# blumentopf_feuchte_messer.net
KiCad netlist of a schematic drawn in EAGLE
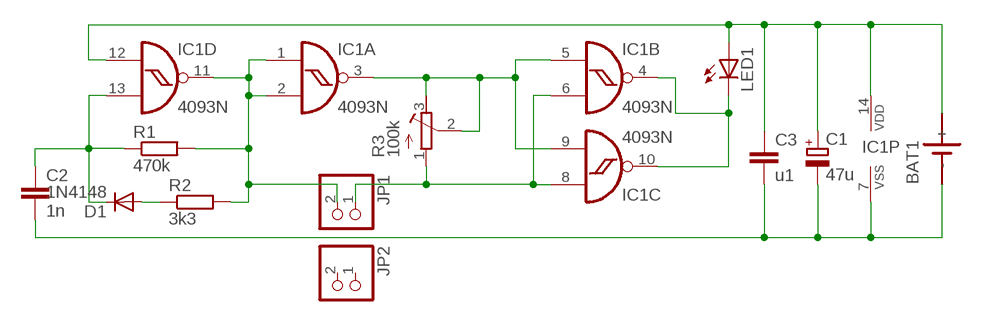
[diagram p0: schematic, sheet 1]

(export (version "E")
  (design (tool "Eeschema 10.0.6"))
  (components
    (comp (ref "BAT1")
      (value "SN2032")
      (footprint "eagle-import:SN2032")
      (libsource (lib "eagle-import") (part "SN2032"))
    )
    (comp (ref "C1")
      (value "47u")
      (footprint "eagle-import:E2,5-5")
      (libsource (lib "eagle-import") (part "CPOL-EUE2.5-5"))
    )
    (comp (ref "C2")
      (value "1n")
      (footprint "eagle-import:C025-025X050")
      (libsource (lib "eagle-import") (part "C-EU025-025X050"))
    )
    (comp (ref "C3")
      (value "u1")
      (footprint "eagle-import:C025-025X050")
      (libsource (lib "eagle-import") (part "C-EU025-025X050"))
    )
    (comp (ref "D1")
      (value "1N4148")
      (footprint "eagle-import:D-2.5")
      (libsource (lib "eagle-import") (part "DIODE-D-2.5"))
    )
    (comp (ref "IC1")
      (value "4093N")
      (footprint "eagle-import:DIL14")
      (libsource (lib "eagle-import") (part "4093N"))
    )
    (comp (ref "JP1")
      (value "PINHD-1X2")
      (footprint "eagle-import:1X02")
      (libsource (lib "eagle-import") (part "PINHD-1X2"))
    )
    (comp (ref "JP2")
      (value "PINHD-1X2")
      (footprint "eagle-import:1X02")
      (libsource (lib "eagle-import") (part "PINHD-1X2"))
    )
    (comp (ref "LED1")
      (value "LED3MM")
      (footprint "eagle-import:LED3MM")
      (libsource (lib "eagle-import") (part "LED3MM"))
    )
    (comp (ref "R1")
      (value "470k")
      (footprint "eagle-import:0207_2V")
      (libsource (lib "eagle-import") (part "R-EU_0207/2V"))
    )
    (comp (ref "R2")
      (value "3k3")
      (footprint "eagle-import:0207_2V")
      (libsource (lib "eagle-import") (part "R-EU_0207/2V"))
    )
    (comp (ref "R3")
      (value "100k")
      (footprint "eagle-import:RTRIM64X")
      (libsource (lib "eagle-import") (part "R-TRIMM64X"))
    )
  )
  (nets
    (net (code "1") (name "Net-(D1-PadA)") (class "Default")
      (node (ref "D1") (pin "A") (pinfunction "A_A") (pintype "passive"))
      (node (ref "R2") (pin "1") (pinfunction "1_1") (pintype "passive"))
    )
    (net (code "2") (name "Net-(IC1A-I0)") (class "Default")
      (node (ref "IC1") (pin "1") (pinfunction "I0_1") (pintype "input"))
      (node (ref "IC1") (pin "11") (pinfunction "O_11") (pintype "output"))
      (node (ref "IC1") (pin "2") (pinfunction "I1_2") (pintype "input"))
      (node (ref "JP1") (pin "2") (pinfunction "2_2") (pintype "passive"))
      (node (ref "R1") (pin "2") (pinfunction "2_2") (pintype "passive"))
      (node (ref "R2") (pin "2") (pinfunction "2_2") (pintype "passive"))
    )
    (net (code "3") (name "Net-(IC1A-O)") (class "Default")
      (node (ref "IC1") (pin "3") (pinfunction "O_3") (pintype "output"))
      (node (ref "IC1") (pin "5") (pinfunction "I0_5") (pintype "input"))
      (node (ref "IC1") (pin "9") (pinfunction "I1_9") (pintype "input"))
      (node (ref "R3") (pin "2") (pinfunction "S_2") (pintype "passive"))
      (node (ref "R3") (pin "3") (pinfunction "E_3") (pintype "passive"))
    )
    (net (code "4") (name "Net-(IC1B-I1)") (class "Default")
      (node (ref "IC1") (pin "6") (pinfunction "I1_6") (pintype "input"))
      (node (ref "IC1") (pin "8") (pinfunction "I0_8") (pintype "input"))
      (node (ref "JP1") (pin "1") (pinfunction "1_1") (pintype "passive"))
      (node (ref "R3") (pin "1") (pinfunction "A_1") (pintype "passive"))
    )
    (net (code "5") (name "Net-(IC1B-O)") (class "Default")
      (node (ref "IC1") (pin "10") (pinfunction "O_10") (pintype "output"))
      (node (ref "IC1") (pin "4") (pinfunction "O_4") (pintype "output"))
      (node (ref "LED1") (pin "K") (pinfunction "C_K") (pintype "passive"))
    )
    (net (code "6") (name "Net-(IC1D-I0)") (class "Default")
      (node (ref "BAT1") (pin "+") (pinfunction "+_+") (pintype "passive"))
      (node (ref "C1") (pin "+") (pinfunction "+_+") (pintype "passive"))
      (node (ref "C3") (pin "1") (pinfunction "1_1") (pintype "passive"))
      (node (ref "IC1") (pin "12") (pinfunction "I0_12") (pintype "input"))
      (node (ref "IC1") (pin "14") (pinfunction "VDD_14") (pintype "power_in"))
      (node (ref "LED1") (pin "A") (pinfunction "A_A") (pintype "passive"))
    )
    (net (code "7") (name "Net-(IC1D-I1)") (class "Default")
      (node (ref "C2") (pin "1") (pinfunction "1_1") (pintype "passive"))
      (node (ref "D1") (pin "C") (pinfunction "C_C") (pintype "passive"))
      (node (ref "IC1") (pin "13") (pinfunction "I1_13") (pintype "input"))
      (node (ref "R1") (pin "1") (pinfunction "1_1") (pintype "passive"))
    )
    (net (code "8") (name "Net-(IC1E-VSS)") (class "Default")
      (node (ref "BAT1") (pin "-") (pinfunction "-_-") (pintype "passive"))
      (node (ref "C1") (pin "-") (pinfunction "-_-") (pintype "passive"))
      (node (ref "C2") (pin "2") (pinfunction "2_2") (pintype "passive"))
      (node (ref "C3") (pin "2") (pinfunction "2_2") (pintype "passive"))
      (node (ref "IC1") (pin "7") (pinfunction "VSS_7") (pintype "power_in"))
    )
    (net (code "9") (name "unconnected-(JP2-Pad1)") (class "Default")
      (node (ref "JP2") (pin "1") (pinfunction "1_1") (pintype "passive"))
    )
    (net (code "10") (name "unconnected-(JP2-Pad2)") (class "Default")
      (node (ref "JP2") (pin "2") (pinfunction "2_2") (pintype "passive"))
    )
  )
)
